# tappytap.net
KiCad netlist of a schematic drawn in EAGLE
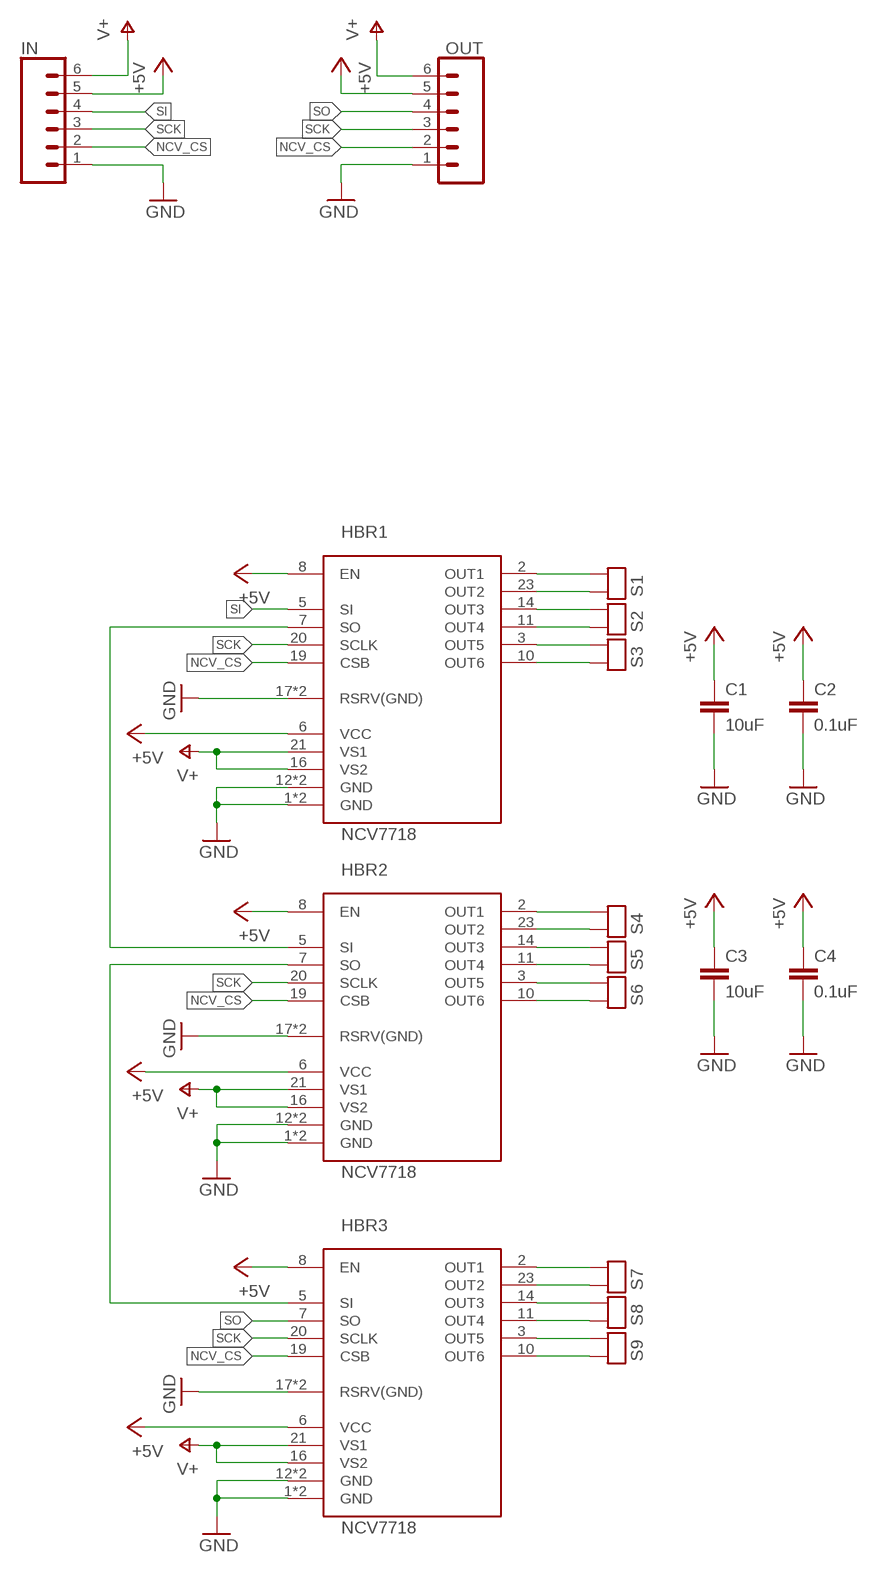
[diagram p0: schematic, sheet 1]

(export (version "E")
  (design (tool "Eeschema 10.0.6"))
  (components
    (comp (ref "C1")
      (value "10uF")
      (footprint "eagle-import:C0603")
      (libsource (lib "eagle-import") (part "C-EUC0603"))
    )
    (comp (ref "C2")
      (value "0.1uF")
      (footprint "eagle-import:C0603")
      (libsource (lib "eagle-import") (part "C-EUC0603"))
    )
    (comp (ref "C3")
      (value "10uF")
      (footprint "eagle-import:C0603")
      (libsource (lib "eagle-import") (part "C-EUC0603"))
    )
    (comp (ref "C4")
      (value "0.1uF")
      (footprint "eagle-import:C0603")
      (libsource (lib "eagle-import") (part "C-EUC0603"))
    )
    (comp (ref "HBR1")
      (value "NCV7718")
      (footprint "eagle-import:SSOP-24")
      (libsource (lib "eagle-import") (part "NCV7718"))
    )
    (comp (ref "HBR2")
      (value "NCV7718")
      (footprint "eagle-import:SSOP-24")
      (libsource (lib "eagle-import") (part "NCV7718"))
    )
    (comp (ref "HBR3")
      (value "NCV7718")
      (footprint "eagle-import:SSOP-24")
      (libsource (lib "eagle-import") (part "NCV7718"))
    )
    (comp (ref "IN")
      (value "CONN_06SILK_FEMALE_PTH")
      (footprint "eagle-import:1X06")
      (libsource (lib "eagle-import") (part "CONN_06SILK_FEMALE_PTH"))
    )
    (comp (ref "OUT")
      (value "CONN_06SILK_FEMALE_PTH")
      (footprint "eagle-import:1X06")
      (libsource (lib "eagle-import") (part "CONN_06SILK_FEMALE_PTH"))
    )
    (comp (ref "S1")
      (value "TP2")
      (footprint "eagle-import:TP2_2MM")
      (libsource (lib "eagle-import") (part "TP2"))
    )
    (comp (ref "S2")
      (value "TP2")
      (footprint "eagle-import:TP2_2MM")
      (libsource (lib "eagle-import") (part "TP2"))
    )
    (comp (ref "S3")
      (value "TP2")
      (footprint "eagle-import:TP2_2MM")
      (libsource (lib "eagle-import") (part "TP2"))
    )
    (comp (ref "S4")
      (value "TP2")
      (footprint "eagle-import:TP2_2MM")
      (libsource (lib "eagle-import") (part "TP2"))
    )
    (comp (ref "S5")
      (value "TP2")
      (footprint "eagle-import:TP2_2MM")
      (libsource (lib "eagle-import") (part "TP2"))
    )
    (comp (ref "S6")
      (value "TP2")
      (footprint "eagle-import:TP2_2MM")
      (libsource (lib "eagle-import") (part "TP2"))
    )
    (comp (ref "S7")
      (value "TP2")
      (footprint "eagle-import:TP2_2MM")
      (libsource (lib "eagle-import") (part "TP2"))
    )
    (comp (ref "S8")
      (value "TP2")
      (footprint "eagle-import:TP2_2MM")
      (libsource (lib "eagle-import") (part "TP2"))
    )
    (comp (ref "S9")
      (value "TP2")
      (footprint "eagle-import:TP2_2MM")
      (libsource (lib "eagle-import") (part "TP2"))
    )
  )
  (nets
    (net (code "1") (name "+5V") (class "Default")
      (node (ref "C1") (pin "1") (pinfunction "1_1") (pintype "passive"))
      (node (ref "C2") (pin "1") (pinfunction "1_1") (pintype "passive"))
      (node (ref "C3") (pin "1") (pinfunction "1_1") (pintype "passive"))
      (node (ref "C4") (pin "1") (pinfunction "1_1") (pintype "passive"))
      (node (ref "HBR1") (pin "6") (pinfunction "VCC_6") (pintype "bidirectional"))
      (node (ref "HBR1") (pin "8") (pinfunction "EN_8") (pintype "bidirectional"))
      (node (ref "HBR2") (pin "6") (pinfunction "VCC_6") (pintype "bidirectional"))
      (node (ref "HBR2") (pin "8") (pinfunction "EN_8") (pintype "bidirectional"))
      (node (ref "HBR3") (pin "6") (pinfunction "VCC_6") (pintype "bidirectional"))
      (node (ref "HBR3") (pin "8") (pinfunction "EN_8") (pintype "bidirectional"))
      (node (ref "IN") (pin "5") (pinfunction "5_5") (pintype "passive"))
      (node (ref "OUT") (pin "5") (pinfunction "5_5") (pintype "passive"))
    )
    (net (code "2") (name "GND") (class "Default")
      (node (ref "C1") (pin "2") (pinfunction "2_2") (pintype "passive"))
      (node (ref "C2") (pin "2") (pinfunction "2_2") (pintype "passive"))
      (node (ref "C3") (pin "2") (pinfunction "2_2") (pintype "passive"))
      (node (ref "C4") (pin "2") (pinfunction "2_2") (pintype "passive"))
      (node (ref "HBR1") (pin "1") (pinfunction "GND_1") (pintype "bidirectional"))
      (node (ref "HBR1") (pin "12") (pinfunction "GND_12") (pintype "bidirectional"))
      (node (ref "HBR1") (pin "13") (pinfunction "GND_13") (pintype "bidirectional"))
      (node (ref "HBR1") (pin "17") (pinfunction "RSRV(GND)_17") (pintype "bidirectional"))
      (node (ref "HBR1") (pin "18") (pinfunction "RSRV(GND)_18") (pintype "bidirectional"))
      (node (ref "HBR1") (pin "24") (pinfunction "GND_24") (pintype "bidirectional"))
      (node (ref "HBR2") (pin "1") (pinfunction "GND_1") (pintype "bidirectional"))
      (node (ref "HBR2") (pin "12") (pinfunction "GND_12") (pintype "bidirectional"))
      (node (ref "HBR2") (pin "13") (pinfunction "GND_13") (pintype "bidirectional"))
      (node (ref "HBR2") (pin "17") (pinfunction "RSRV(GND)_17") (pintype "bidirectional"))
      (node (ref "HBR2") (pin "18") (pinfunction "RSRV(GND)_18") (pintype "bidirectional"))
      (node (ref "HBR2") (pin "24") (pinfunction "GND_24") (pintype "bidirectional"))
      (node (ref "HBR3") (pin "1") (pinfunction "GND_1") (pintype "bidirectional"))
      (node (ref "HBR3") (pin "12") (pinfunction "GND_12") (pintype "bidirectional"))
      (node (ref "HBR3") (pin "13") (pinfunction "GND_13") (pintype "bidirectional"))
      (node (ref "HBR3") (pin "17") (pinfunction "RSRV(GND)_17") (pintype "bidirectional"))
      (node (ref "HBR3") (pin "18") (pinfunction "RSRV(GND)_18") (pintype "bidirectional"))
      (node (ref "HBR3") (pin "24") (pinfunction "GND_24") (pintype "bidirectional"))
      (node (ref "IN") (pin "1") (pinfunction "1_1") (pintype "passive"))
      (node (ref "OUT") (pin "1") (pinfunction "1_1") (pintype "passive"))
    )
    (net (code "3") (name "NCV_CS") (class "Default")
      (node (ref "HBR1") (pin "19") (pinfunction "CSB_19") (pintype "bidirectional"))
      (node (ref "HBR2") (pin "19") (pinfunction "CSB_19") (pintype "bidirectional"))
      (node (ref "HBR3") (pin "19") (pinfunction "CSB_19") (pintype "bidirectional"))
      (node (ref "IN") (pin "2") (pinfunction "2_2") (pintype "passive"))
      (node (ref "OUT") (pin "2") (pinfunction "2_2") (pintype "passive"))
    )
    (net (code "4") (name "Net-(HBR1-OUT1)") (class "Default")
      (node (ref "HBR1") (pin "2") (pinfunction "OUT1_2") (pintype "bidirectional"))
      (node (ref "S1") (pin "P$1") (pinfunction "0_P$1") (pintype "bidirectional"))
    )
    (net (code "5") (name "Net-(HBR1-OUT2)") (class "Default")
      (node (ref "HBR1") (pin "23") (pinfunction "OUT2_23") (pintype "bidirectional"))
      (node (ref "S1") (pin "P$2") (pinfunction "1_P$2") (pintype "bidirectional"))
    )
    (net (code "6") (name "Net-(HBR1-OUT3)") (class "Default")
      (node (ref "HBR1") (pin "14") (pinfunction "OUT3_14") (pintype "bidirectional"))
      (node (ref "S2") (pin "P$1") (pinfunction "0_P$1") (pintype "bidirectional"))
    )
    (net (code "7") (name "Net-(HBR1-OUT4)") (class "Default")
      (node (ref "HBR1") (pin "11") (pinfunction "OUT4_11") (pintype "bidirectional"))
      (node (ref "S2") (pin "P$2") (pinfunction "1_P$2") (pintype "bidirectional"))
    )
    (net (code "8") (name "Net-(HBR1-OUT5)") (class "Default")
      (node (ref "HBR1") (pin "3") (pinfunction "OUT5_3") (pintype "bidirectional"))
      (node (ref "S3") (pin "P$1") (pinfunction "0_P$1") (pintype "bidirectional"))
    )
    (net (code "9") (name "Net-(HBR1-OUT6)") (class "Default")
      (node (ref "HBR1") (pin "10") (pinfunction "OUT6_10") (pintype "bidirectional"))
      (node (ref "S3") (pin "P$2") (pinfunction "1_P$2") (pintype "bidirectional"))
    )
    (net (code "10") (name "Net-(HBR1-SO)") (class "Default")
      (node (ref "HBR1") (pin "7") (pinfunction "SO_7") (pintype "bidirectional"))
      (node (ref "HBR2") (pin "5") (pinfunction "SI_5") (pintype "bidirectional"))
    )
    (net (code "11") (name "Net-(HBR2-OUT1)") (class "Default")
      (node (ref "HBR2") (pin "2") (pinfunction "OUT1_2") (pintype "bidirectional"))
      (node (ref "S4") (pin "P$1") (pinfunction "0_P$1") (pintype "bidirectional"))
    )
    (net (code "12") (name "Net-(HBR2-OUT2)") (class "Default")
      (node (ref "HBR2") (pin "23") (pinfunction "OUT2_23") (pintype "bidirectional"))
      (node (ref "S4") (pin "P$2") (pinfunction "1_P$2") (pintype "bidirectional"))
    )
    (net (code "13") (name "Net-(HBR2-OUT3)") (class "Default")
      (node (ref "HBR2") (pin "14") (pinfunction "OUT3_14") (pintype "bidirectional"))
      (node (ref "S5") (pin "P$1") (pinfunction "0_P$1") (pintype "bidirectional"))
    )
    (net (code "14") (name "Net-(HBR2-OUT4)") (class "Default")
      (node (ref "HBR2") (pin "11") (pinfunction "OUT4_11") (pintype "bidirectional"))
      (node (ref "S5") (pin "P$2") (pinfunction "1_P$2") (pintype "bidirectional"))
    )
    (net (code "15") (name "Net-(HBR2-OUT5)") (class "Default")
      (node (ref "HBR2") (pin "3") (pinfunction "OUT5_3") (pintype "bidirectional"))
      (node (ref "S6") (pin "P$1") (pinfunction "0_P$1") (pintype "bidirectional"))
    )
    (net (code "16") (name "Net-(HBR2-OUT6)") (class "Default")
      (node (ref "HBR2") (pin "10") (pinfunction "OUT6_10") (pintype "bidirectional"))
      (node (ref "S6") (pin "P$2") (pinfunction "1_P$2") (pintype "bidirectional"))
    )
    (net (code "17") (name "Net-(HBR2-SO)") (class "Default")
      (node (ref "HBR2") (pin "7") (pinfunction "SO_7") (pintype "bidirectional"))
      (node (ref "HBR3") (pin "5") (pinfunction "SI_5") (pintype "bidirectional"))
    )
    (net (code "18") (name "Net-(HBR3-OUT1)") (class "Default")
      (node (ref "HBR3") (pin "2") (pinfunction "OUT1_2") (pintype "bidirectional"))
      (node (ref "S7") (pin "P$1") (pinfunction "0_P$1") (pintype "bidirectional"))
    )
    (net (code "19") (name "Net-(HBR3-OUT2)") (class "Default")
      (node (ref "HBR3") (pin "23") (pinfunction "OUT2_23") (pintype "bidirectional"))
      (node (ref "S7") (pin "P$2") (pinfunction "1_P$2") (pintype "bidirectional"))
    )
    (net (code "20") (name "Net-(HBR3-OUT3)") (class "Default")
      (node (ref "HBR3") (pin "14") (pinfunction "OUT3_14") (pintype "bidirectional"))
      (node (ref "S8") (pin "P$1") (pinfunction "0_P$1") (pintype "bidirectional"))
    )
    (net (code "21") (name "Net-(HBR3-OUT4)") (class "Default")
      (node (ref "HBR3") (pin "11") (pinfunction "OUT4_11") (pintype "bidirectional"))
      (node (ref "S8") (pin "P$2") (pinfunction "1_P$2") (pintype "bidirectional"))
    )
    (net (code "22") (name "Net-(HBR3-OUT5)") (class "Default")
      (node (ref "HBR3") (pin "3") (pinfunction "OUT5_3") (pintype "bidirectional"))
      (node (ref "S9") (pin "P$1") (pinfunction "0_P$1") (pintype "bidirectional"))
    )
    (net (code "23") (name "Net-(HBR3-OUT6)") (class "Default")
      (node (ref "HBR3") (pin "10") (pinfunction "OUT6_10") (pintype "bidirectional"))
      (node (ref "S9") (pin "P$2") (pinfunction "1_P$2") (pintype "bidirectional"))
    )
    (net (code "24") (name "SCK") (class "Default")
      (node (ref "HBR1") (pin "20") (pinfunction "SCLK_20") (pintype "bidirectional"))
      (node (ref "HBR2") (pin "20") (pinfunction "SCLK_20") (pintype "bidirectional"))
      (node (ref "HBR3") (pin "20") (pinfunction "SCLK_20") (pintype "bidirectional"))
      (node (ref "IN") (pin "3") (pinfunction "3_3") (pintype "passive"))
      (node (ref "OUT") (pin "3") (pinfunction "3_3") (pintype "passive"))
    )
    (net (code "25") (name "SI") (class "Default")
      (node (ref "HBR1") (pin "5") (pinfunction "SI_5") (pintype "bidirectional"))
      (node (ref "IN") (pin "4") (pinfunction "4_4") (pintype "passive"))
    )
    (net (code "26") (name "SO") (class "Default")
      (node (ref "HBR3") (pin "7") (pinfunction "SO_7") (pintype "bidirectional"))
      (node (ref "OUT") (pin "4") (pinfunction "4_4") (pintype "passive"))
    )
    (net (code "27") (name "V+") (class "Default")
      (node (ref "HBR1") (pin "16") (pinfunction "VS2_16") (pintype "bidirectional"))
      (node (ref "HBR1") (pin "21") (pinfunction "VS1_21") (pintype "bidirectional"))
      (node (ref "HBR2") (pin "16") (pinfunction "VS2_16") (pintype "bidirectional"))
      (node (ref "HBR2") (pin "21") (pinfunction "VS1_21") (pintype "bidirectional"))
      (node (ref "HBR3") (pin "16") (pinfunction "VS2_16") (pintype "bidirectional"))
      (node (ref "HBR3") (pin "21") (pinfunction "VS1_21") (pintype "bidirectional"))
      (node (ref "IN") (pin "6") (pinfunction "6_6") (pintype "passive"))
      (node (ref "OUT") (pin "6") (pinfunction "6_6") (pintype "passive"))
    )
  )
)
